# radar.net
KiCad netlist of a schematic drawn in Altium Designer
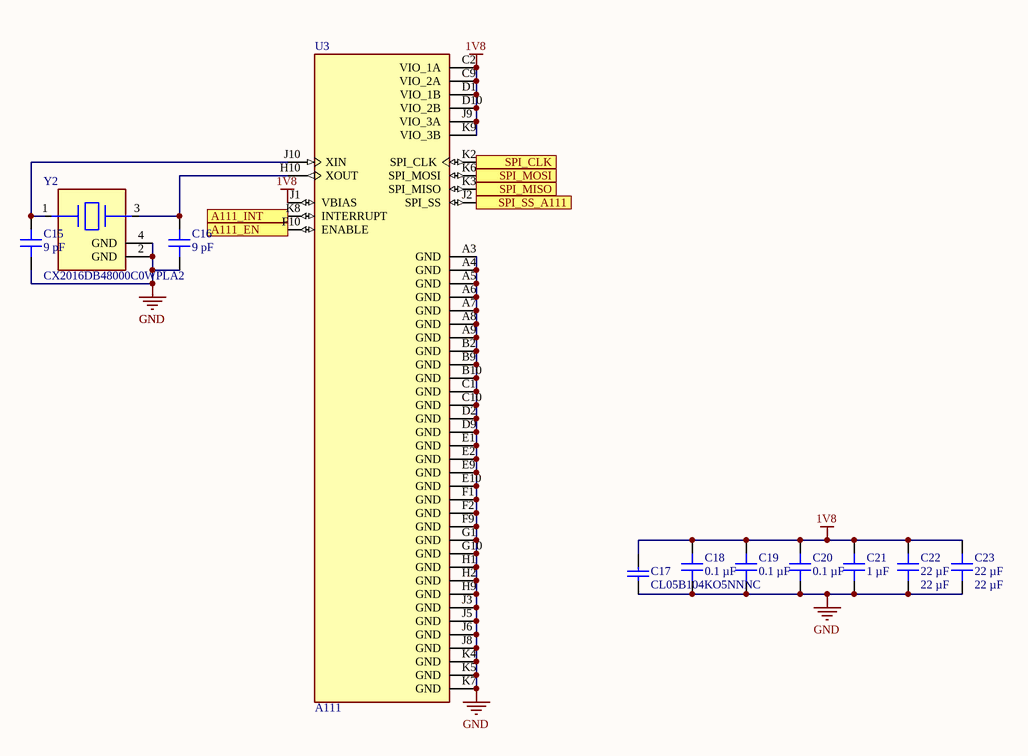
[diagram p0: radar.SchDoc]

(export (version "E")
  (design (tool "Eeschema 10.0.6"))
  (components
    (comp (ref "C15")
      (value "9 pF")
      (footprint "CAP 0402_1005")
      (description "CAP CER 9PF 50V C0G 0402")
      (fields
        (field (name "PART NUMBER") "CGA2B2C0G1H090D050BA")
        (field (name "MANUFACTURER") "TDK Corporation")
      )
      (libsource (lib "Celestial Altium Library - altium_library") (part "Capacitor"))
    )
    (comp (ref "C16")
      (value "9 pF")
      (footprint "CAP 0402_1005")
      (description "CAP CER 9PF 50V C0G 0402")
      (fields
        (field (name "PART NUMBER") "CGA2B2C0G1H090D050BA")
        (field (name "MANUFACTURER") "TDK Corporation")
      )
      (libsource (lib "Celestial Altium Library - altium_library") (part "Capacitor"))
    )
    (comp (ref "C17")
      (value "CL05B104KO5NNNC")
      (footprint "CAPC1050X55X23ML05T13")
      (description "Chip Capacitor, 100 nF, +/- 10%, 16 V, -55 to 125 degC, 0402 (1005 Metric), RoHS, Tape and Reel")
      (fields (field (name "MANUFACTURER") "Samsung Electro-Mechanics"))
      (libsource (lib "Altium Content Vault") (part "CAP-NP-2"))
    )
    (comp (ref "C18")
      (value "0.1 µF")
      (footprint "CAP 0402_1005")
      (description "CAP CER 0.1UF 4V X5R 0402")
      (fields (field (name "PART NUMBER") "C0402C104K7PAC7867") (field (name "MANUFACTURER") "KEMET"))
      (libsource (lib "Celestial Altium Library - altium_library") (part "Capacitor"))
    )
    (comp (ref "C19")
      (value "0.1 µF")
      (footprint "CAP 0402_1005")
      (description "CAP CER 0.1UF 4V X5R 0402")
      (fields (field (name "PART NUMBER") "C0402C104K7PAC7867") (field (name "MANUFACTURER") "KEMET"))
      (libsource (lib "Celestial Altium Library - altium_library") (part "Capacitor"))
    )
    (comp (ref "C20")
      (value "0.1 µF")
      (footprint "CAP 0402_1005")
      (description "CAP CER 0.1UF 4V X5R 0402")
      (fields (field (name "PART NUMBER") "C0402C104K7PAC7867") (field (name "MANUFACTURER") "KEMET"))
      (libsource (lib "Celestial Altium Library - altium_library") (part "Capacitor"))
    )
    (comp (ref "C21")
      (value "1 µF")
      (footprint "CAP 0402_1005")
      (description "CAP CER 1UF 10V X6S 0402")
      (fields (field (name "PART NUMBER") "LMK105C6105KV-F") (field (name "MANUFACTURER") "Taiyo Yuden"))
      (libsource (lib "Celestial Altium Library - altium_library") (part "Capacitor"))
    )
    (comp (ref "C22")
      (value "22 µF")
      (footprint "CAP 0603_1608")
      (description "CAP CER 22UF 10V X5R 0603")
      (fields (field (name "PART NUMBER") "0603ZD226MAT2A") (field (name "ALTIUM_VALUE") "22 µF"))
      (libsource (lib "Celestial Altium Library - altium_library") (part "Capacitor"))
    )
    (comp (ref "C23")
      (value "22 µF")
      (footprint "CAP 0603_1608")
      (description "CAP CER 22UF 10V X5R 0603")
      (fields (field (name "PART NUMBER") "0603ZD226MAT2A") (field (name "ALTIUM_VALUE") "22 µF"))
      (libsource (lib "Celestial Altium Library - altium_library") (part "Capacitor"))
    )
    (comp (ref "U3")
      (value "A111")
      (footprint "BGA50N50P10X10_520X550X89N")
      (description "A111 Radar Sensor")
      (fields (field (name "MF") "acconeer"))
      (libsource (lib "A111") (part "A111"))
    )
    (comp (ref "Y2")
      (value "CX2016DB48000C0WPLA2")
      (footprint "FP-CX2016DB48000C0WPLA2-MFG")
      (description "CRYSTAL 48.0000MHZ 7PF SMD")
      (fields
        (field (name "TOLERANCE") "20ppm")
        (field (name "OCTOPART") "https://octopart.com/cx2016db48000c0wpla2-avx+%2F+kyocera-52876167")
      )
      (libsource (lib "Altium Content Vault") (part "5d94e547cd785c846f3f8944f2e9776"))
    )
  )
  (nets
    (net (code "1") (name "/A111_EN") (class "Default")
      (node (ref "U3") (pin "F10") (pinfunction "ENABLE_F10") (pintype "bidirectional"))
    )
    (net (code "2") (name "/A111_INT") (class "Default")
      (node (ref "U3") (pin "K8") (pinfunction "INTERRUPT_K8") (pintype "bidirectional"))
    )
    (net (code "3") (name "/SPI_CLK") (class "Default")
      (node (ref "U3") (pin "K2") (pinfunction "SPI_CLK_K2") (pintype "bidirectional"))
    )
    (net (code "4") (name "/SPI_MISO") (class "Default")
      (node (ref "U3") (pin "K3") (pinfunction "SPI_MISO_K3") (pintype "bidirectional"))
    )
    (net (code "5") (name "/SPI_MOSI") (class "Default")
      (node (ref "U3") (pin "K6") (pinfunction "SPI_MOSI_K6") (pintype "bidirectional"))
    )
    (net (code "6") (name "/SPI_SS_A111") (class "Default")
      (node (ref "U3") (pin "J2") (pinfunction "SPI_SS_J2") (pintype "bidirectional"))
    )
    (net (code "7") (name "1V8") (class "Default")
      (node (ref "C17") (pin "2") (pinfunction "2_2") (pintype "passive"))
      (node (ref "C18") (pin "2") (pinfunction "2_2") (pintype "passive"))
      (node (ref "C19") (pin "2") (pinfunction "2_2") (pintype "passive"))
      (node (ref "C20") (pin "2") (pinfunction "2_2") (pintype "passive"))
      (node (ref "C21") (pin "2") (pinfunction "2_2") (pintype "passive"))
      (node (ref "C22") (pin "1") (pinfunction "1_1") (pintype "passive"))
      (node (ref "C23") (pin "2") (pinfunction "2_2") (pintype "passive"))
      (node (ref "U3") (pin "C2") (pinfunction "VIO_1A_C2") (pintype "power_in"))
      (node (ref "U3") (pin "C9") (pinfunction "VIO_2A_C9") (pintype "power_in"))
      (node (ref "U3") (pin "D1") (pinfunction "VIO_1B_D1") (pintype "power_in"))
      (node (ref "U3") (pin "D10") (pinfunction "VIO_2B_D10") (pintype "power_in"))
      (node (ref "U3") (pin "J1") (pinfunction "VBIAS_J1") (pintype "bidirectional"))
      (node (ref "U3") (pin "J9") (pinfunction "VIO_3A_J9") (pintype "power_in"))
      (node (ref "U3") (pin "K9") (pinfunction "VIO_3B_K9") (pintype "power_in"))
    )
    (net (code "8") (name "GND") (class "Default")
      (node (ref "C15") (pin "1") (pinfunction "1_1") (pintype "passive"))
      (node (ref "C16") (pin "1") (pinfunction "1_1") (pintype "passive"))
      (node (ref "C17") (pin "1") (pinfunction "1_1") (pintype "passive"))
      (node (ref "C18") (pin "1") (pinfunction "1_1") (pintype "passive"))
      (node (ref "C19") (pin "1") (pinfunction "1_1") (pintype "passive"))
      (node (ref "C20") (pin "1") (pinfunction "1_1") (pintype "passive"))
      (node (ref "C21") (pin "1") (pinfunction "1_1") (pintype "passive"))
      (node (ref "C22") (pin "2") (pinfunction "2_2") (pintype "passive"))
      (node (ref "C23") (pin "1") (pinfunction "1_1") (pintype "passive"))
      (node (ref "U3") (pin "A3") (pinfunction "GND_A3") (pintype "power_in"))
      (node (ref "U3") (pin "A4") (pinfunction "GND_A4") (pintype "power_in"))
      (node (ref "U3") (pin "A5") (pinfunction "GND_A5") (pintype "power_in"))
      (node (ref "U3") (pin "A6") (pinfunction "GND_A6") (pintype "power_in"))
      (node (ref "U3") (pin "A7") (pinfunction "GND_A7") (pintype "power_in"))
      (node (ref "U3") (pin "A8") (pinfunction "GND_A8") (pintype "power_in"))
      (node (ref "U3") (pin "A9") (pinfunction "GND_A9") (pintype "power_in"))
      (node (ref "U3") (pin "B10") (pinfunction "GND_B10") (pintype "power_in"))
      (node (ref "U3") (pin "B2") (pinfunction "GND_B2") (pintype "power_in"))
      (node (ref "U3") (pin "B9") (pinfunction "GND_B9") (pintype "power_in"))
      (node (ref "U3") (pin "C1") (pinfunction "GND_C1") (pintype "power_in"))
      (node (ref "U3") (pin "C10") (pinfunction "GND_C10") (pintype "power_in"))
      (node (ref "U3") (pin "D2") (pinfunction "GND_D2") (pintype "power_in"))
      (node (ref "U3") (pin "D9") (pinfunction "GND_D9") (pintype "power_in"))
      (node (ref "U3") (pin "E1") (pinfunction "GND_E1") (pintype "power_in"))
      (node (ref "U3") (pin "E10") (pinfunction "GND_E10") (pintype "power_in"))
      (node (ref "U3") (pin "E2") (pinfunction "GND_E2") (pintype "power_in"))
      (node (ref "U3") (pin "E9") (pinfunction "GND_E9") (pintype "power_in"))
      (node (ref "U3") (pin "F1") (pinfunction "GND_F1") (pintype "power_in"))
      (node (ref "U3") (pin "F2") (pinfunction "GND_F2") (pintype "power_in"))
      (node (ref "U3") (pin "F9") (pinfunction "GND_F9") (pintype "power_in"))
      (node (ref "U3") (pin "G1") (pinfunction "GND_G1") (pintype "power_in"))
      (node (ref "U3") (pin "G10") (pinfunction "GND_G10") (pintype "power_in"))
      (node (ref "U3") (pin "H1") (pinfunction "GND_H1") (pintype "power_in"))
      (node (ref "U3") (pin "H2") (pinfunction "GND_H2") (pintype "power_in"))
      (node (ref "U3") (pin "H9") (pinfunction "GND_H9") (pintype "power_in"))
      (node (ref "U3") (pin "J3") (pinfunction "GND_J3") (pintype "power_in"))
      (node (ref "U3") (pin "J5") (pinfunction "GND_J5") (pintype "power_in"))
      (node (ref "U3") (pin "J6") (pinfunction "GND_J6") (pintype "power_in"))
      (node (ref "U3") (pin "J8") (pinfunction "GND_J8") (pintype "power_in"))
      (node (ref "U3") (pin "K4") (pinfunction "GND_K4") (pintype "power_in"))
      (node (ref "U3") (pin "K5") (pinfunction "GND_K5") (pintype "power_in"))
      (node (ref "U3") (pin "K7") (pinfunction "GND_K7") (pintype "power_in"))
      (node (ref "Y2") (pin "2") (pinfunction "GND_2") (pintype "power_in"))
      (node (ref "Y2") (pin "4") (pinfunction "GND_4") (pintype "power_in"))
    )
    (net (code "9") (name "Net-(U3-XIN)") (class "Default")
      (node (ref "C15") (pin "2") (pinfunction "2_2") (pintype "passive"))
      (node (ref "U3") (pin "J10") (pinfunction "XIN_J10") (pintype "input"))
      (node (ref "Y2") (pin "1") (pinfunction "1_HOT_1") (pintype "passive"))
    )
    (net (code "10") (name "Net-(U3-XOUT)") (class "Default")
      (node (ref "C16") (pin "2") (pinfunction "2_2") (pintype "passive"))
      (node (ref "U3") (pin "H10") (pinfunction "XOUT_H10") (pintype "output"))
      (node (ref "Y2") (pin "3") (pinfunction "2_HOT_3") (pintype "passive"))
    )
  )
)
